# RP2040.net
KiCad netlist of a schematic drawn in Altium Designer
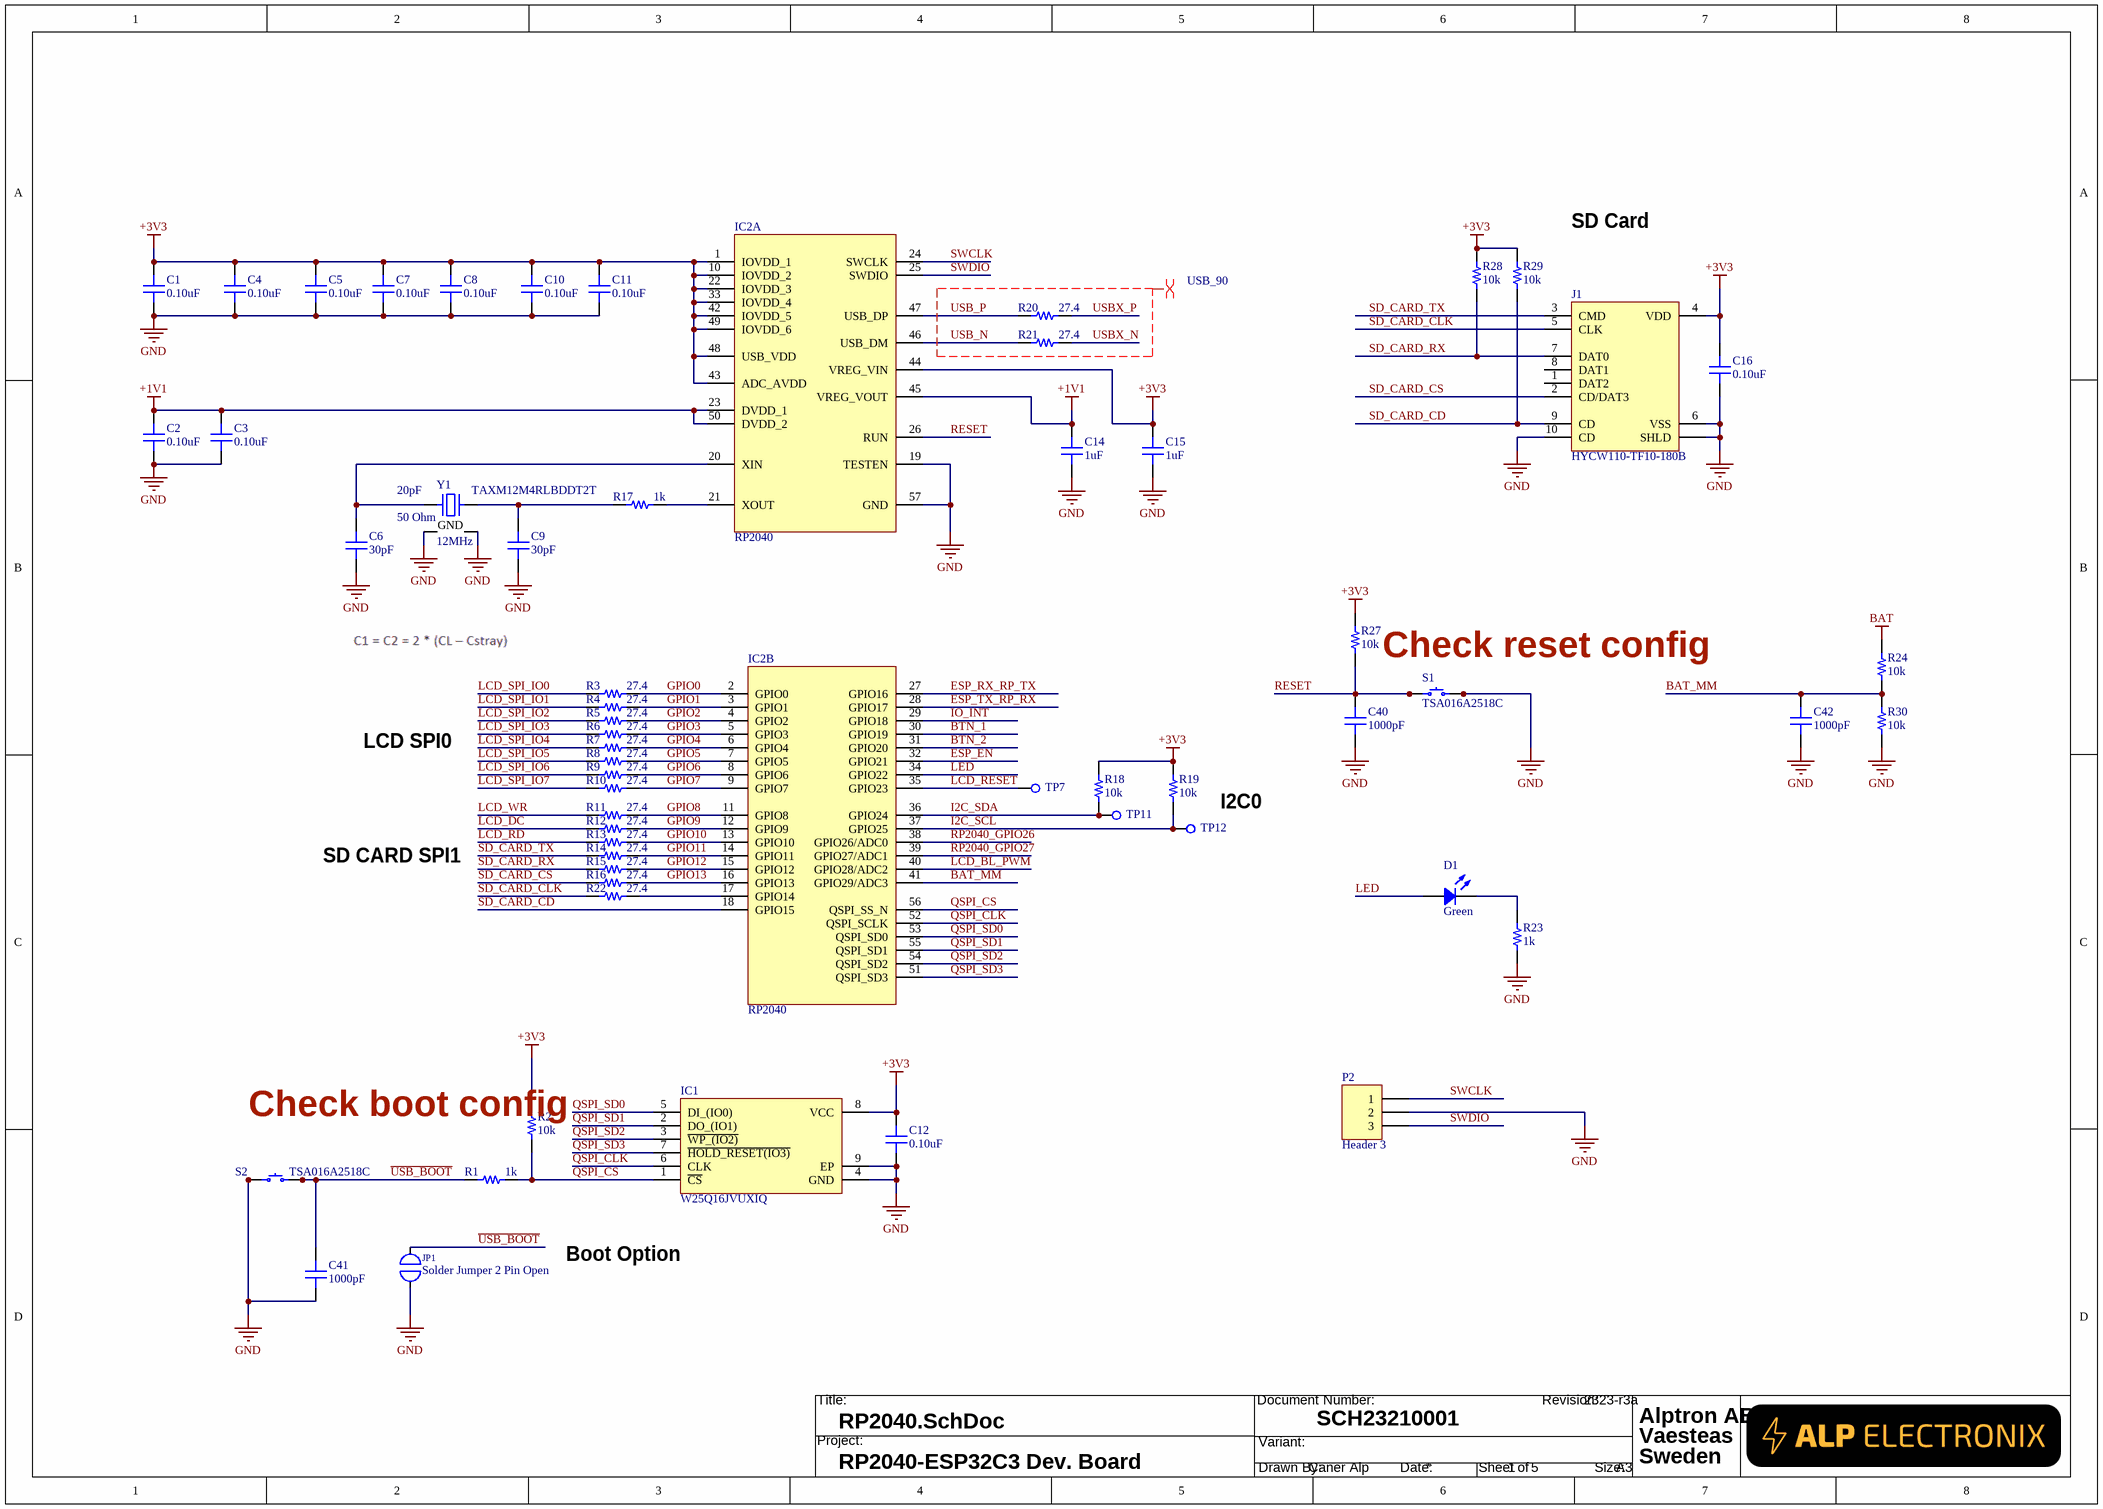
[diagram p0: RP2040.SchDoc]

(export (version "E")
  (design (tool "Eeschema 10.0.6"))
  (components
    (comp (ref "C1")
      (value "0.10uF")
      (footprint "CAP 0402/1005")
      (description "CAP CER 0.1UF 10V X5R 0402")
      (fields (field (name "PART NUMBER") "LMK105BJ104KV-F") (field (name "MANUFACTURER") "Taiyo Yuden"))
      (libsource (lib "Celestial Library Database") (part "Capacitor"))
    )
    (comp (ref "C2")
      (value "0.10uF")
      (footprint "CAP 0402/1005")
      (description "CAP CER 0.1UF 10V X5R 0402")
      (fields (field (name "PART NUMBER") "LMK105BJ104KV-F") (field (name "MANUFACTURER") "Taiyo Yuden"))
      (libsource (lib "Celestial Library Database") (part "Capacitor"))
    )
    (comp (ref "C3")
      (value "0.10uF")
      (footprint "CAP 0402/1005")
      (description "CAP CER 0.1UF 10V X5R 0402")
      (fields (field (name "PART NUMBER") "LMK105BJ104KV-F") (field (name "MANUFACTURER") "Taiyo Yuden"))
      (libsource (lib "Celestial Library Database") (part "Capacitor"))
    )
    (comp (ref "C4")
      (value "0.10uF")
      (footprint "CAP 0402/1005")
      (description "CAP CER 0.1UF 10V X5R 0402")
      (fields (field (name "PART NUMBER") "LMK105BJ104KV-F") (field (name "MANUFACTURER") "Taiyo Yuden"))
      (libsource (lib "Celestial Library Database") (part "Capacitor"))
    )
    (comp (ref "C5")
      (value "0.10uF")
      (footprint "CAP 0402/1005")
      (description "CAP CER 0.1UF 10V X5R 0402")
      (fields (field (name "PART NUMBER") "LMK105BJ104KV-F") (field (name "MANUFACTURER") "Taiyo Yuden"))
      (libsource (lib "Celestial Library Database") (part "Capacitor"))
    )
    (comp (ref "C6")
      (value "30pF")
      (footprint "CAP 0402/1005")
      (description "CAP CER 30PF 50V NP0 0402")
      (fields
        (field (name "PART NUMBER") "GRM1555C1H300JA01D")
        (field (name "MANUFACTURER") "Murata Electronics North America")
      )
      (libsource (lib "Celestial Library Database") (part "Capacitor"))
    )
    (comp (ref "C7")
      (value "0.10uF")
      (footprint "CAP 0402/1005")
      (description "CAP CER 0.1UF 10V X5R 0402")
      (fields (field (name "PART NUMBER") "LMK105BJ104KV-F") (field (name "MANUFACTURER") "Taiyo Yuden"))
      (libsource (lib "Celestial Library Database") (part "Capacitor"))
    )
    (comp (ref "C8")
      (value "0.10uF")
      (footprint "CAP 0402/1005")
      (description "CAP CER 0.1UF 10V X5R 0402")
      (fields (field (name "PART NUMBER") "LMK105BJ104KV-F") (field (name "MANUFACTURER") "Taiyo Yuden"))
      (libsource (lib "Celestial Library Database") (part "Capacitor"))
    )
    (comp (ref "C9")
      (value "30pF")
      (footprint "CAP 0402/1005")
      (description "CAP CER 30PF 50V NP0 0402")
      (fields
        (field (name "PART NUMBER") "GRM1555C1H300JA01D")
        (field (name "MANUFACTURER") "Murata Electronics North America")
      )
      (libsource (lib "Celestial Library Database") (part "Capacitor"))
    )
    (comp (ref "C10")
      (value "0.10uF")
      (footprint "CAP 0402/1005")
      (description "CAP CER 0.1UF 10V X5R 0402")
      (fields (field (name "PART NUMBER") "LMK105BJ104KV-F") (field (name "MANUFACTURER") "Taiyo Yuden"))
      (libsource (lib "Celestial Library Database") (part "Capacitor"))
    )
    (comp (ref "C11")
      (value "0.10uF")
      (footprint "CAP 0402/1005")
      (description "CAP CER 0.1UF 10V X5R 0402")
      (fields (field (name "PART NUMBER") "LMK105BJ104KV-F") (field (name "MANUFACTURER") "Taiyo Yuden"))
      (libsource (lib "Celestial Library Database") (part "Capacitor"))
    )
    (comp (ref "C12")
      (value "0.10uF")
      (footprint "CAP 0402/1005")
      (description "CAP CER 0.1UF 10V X5R 0402")
      (fields (field (name "PART NUMBER") "LMK105BJ104KV-F") (field (name "MANUFACTURER") "Taiyo Yuden"))
      (libsource (lib "Celestial Library Database") (part "Capacitor"))
    )
    (comp (ref "C14")
      (value "1uF")
      (footprint "CAP 0402/1005")
      (description "CAP CER 1UF 6.3V X7R 0402")
      (fields
        (field (name "PART NUMBER") "GRM155R70J105KA12D")
        (field (name "MANUFACTURER") "Murata Electronics North America")
      )
      (libsource (lib "Celestial Library Database") (part "Capacitor"))
    )
    (comp (ref "C15")
      (value "1uF")
      (footprint "CAP 0402/1005")
      (description "CAP CER 1UF 6.3V X7R 0402")
      (fields
        (field (name "PART NUMBER") "GRM155R70J105KA12D")
        (field (name "MANUFACTURER") "Murata Electronics North America")
      )
      (libsource (lib "Celestial Library Database") (part "Capacitor"))
    )
    (comp (ref "C16")
      (value "0.10uF")
      (footprint "CAP 0402/1005")
      (description "CAP CER 0.1UF 10V X5R 0402")
      (fields (field (name "PART NUMBER") "LMK105BJ104KV-F") (field (name "MANUFACTURER") "Taiyo Yuden"))
      (libsource (lib "Celestial Library Database") (part "Capacitor"))
    )
    (comp (ref "C40")
      (value "1000pF")
      (footprint "CAP 0402/1005")
      (description "CAP CER 1000PF 50V C0G 0402")
      (fields
        (field (name "PART NUMBER") "C1005C0G1H102J050BA")
        (field (name "MANUFACTURER") "TDK Corporation")
      )
      (libsource (lib "Celestial Library Database") (part "Capacitor"))
    )
    (comp (ref "C41")
      (value "1000pF")
      (footprint "CAP 0402/1005")
      (description "CAP CER 1000PF 50V C0G 0402")
      (fields
        (field (name "PART NUMBER") "C1005C0G1H102J050BA")
        (field (name "MANUFACTURER") "TDK Corporation")
      )
      (libsource (lib "Celestial Library Database") (part "Capacitor"))
    )
    (comp (ref "C42")
      (value "1000pF")
      (footprint "CAP 0402/1005")
      (description "CAP CER 1000PF 50V C0G 0402")
      (fields
        (field (name "PART NUMBER") "C1005C0G1H102J050BA")
        (field (name "MANUFACTURER") "TDK Corporation")
      )
      (libsource (lib "Celestial Library Database") (part "Capacitor"))
    )
    (comp (ref "D1")
      (value "Green")
      (footprint "LED 0603/1608 GREEN")
      (description "LED GREEN DIFFUSED 0603 SMD")
      (fields
        (field (name "PART NUMBER") "HSMQ-C191")
        (field (name "MANUFACTURER") "Avago Technologies US Inc.")
      )
      (libsource (lib "Celestial Library Database") (part "LED"))
    )
    (comp (ref "IC1")
      (value "W25Q16JVUXIQ")
      (footprint "RP2040_ESP32-C3 Dev Board PCB Lib:SON50P300X200X60-9N")
      (description "Integrated Circuit")
      (libsource (lib "RP2040_ESP32-C3 Dev Board SCH Lib") (part "W25Q16JVUXIQ"))
    )
    (comp (ref "IC2")
      (value "RP2040")
      (footprint "RP2040_ESP32-C3 Dev Board PCB Lib:QFN40P700X700X90-57N-D")
      (description "Integrated Circuit")
      (libsource (lib "RP2040_ESP32-C3 Dev Board SCH Lib") (part "RP2040"))
    )
    (comp (ref "J1")
      (value "HYCW110-TF10-180B")
      (footprint "HYCW110-TF10-180B")
      (description "MICRO SD PUSH/PUSH SMALL 8C")
      (fields (field (name "MANUFACTURER") "SHOU HAN"))
      (libsource (lib "RP2040_ESP32-C3 Dev Board SCH Lib") (part "HYCW110-TF10-180B"))
    )
    (comp (ref "JP1")
      (value "Solder Jumper 2 Pin Open")
      (footprint "Jumper:SolderJumper-2_P1.3mm_Open_RoundedPad1.0x1.5mm")
      (libsource (lib "Jumper") (part "SolderJumper_2_Open"))
    )
    (comp (ref "P2")
      (value "Header 3")
      (footprint "RP2040_ESP32-C3 Dev Board PCB Lib:3 Pads for SBW")
      (description "Header, 3-Pin")
      (fields (field (name "PUBLISHER") "Altium Limited"))
      (libsource (lib "Miscellaneous Connectors") (part "Header 3"))
    )
    (comp (ref "R1")
      (value "1k")
      (footprint "RES 0402/1005")
      (description "RES SMD 1K OHM 5% 1/10W 0402")
      (fields
        (field (name "PART NUMBER") "ERJ-2GEJ102X")
        (field (name "MANUFACTURER") "Panasonic Electronic Components")
      )
      (libsource (lib "Celestial Library Database") (part "Resistor"))
    )
    (comp (ref "R2")
      (value "10k")
      (footprint "RES 0402/1005")
      (description "RES SMD 10K OHM 5% 1/16W 0402")
      (fields (field (name "PART NUMBER") "RC0402JR-0710KL") (field (name "MANUFACTURER") "Yageo"))
      (libsource (lib "Celestial Library Database") (part "Resistor"))
    )
    (comp (ref "R3")
      (value "27.4")
      (footprint "RES 0402/1005")
      (description "RES SMD 27.4 OHM 1% 1/10W 0402")
      (fields
        (field (name "PART NUMBER") "ERJ-2RKF27R4X")
        (field (name "MANUFACTURER") "Panasonic Electronic Components")
      )
      (libsource (lib "Celestial Library Database") (part "Resistor"))
    )
    (comp (ref "R4")
      (value "27.4")
      (footprint "RES 0402/1005")
      (description "RES SMD 27.4 OHM 1% 1/10W 0402")
      (fields
        (field (name "PART NUMBER") "ERJ-2RKF27R4X")
        (field (name "MANUFACTURER") "Panasonic Electronic Components")
      )
      (libsource (lib "Celestial Library Database") (part "Resistor"))
    )
    (comp (ref "R5")
      (value "27.4")
      (footprint "RES 0402/1005")
      (description "RES SMD 27.4 OHM 1% 1/10W 0402")
      (fields
        (field (name "PART NUMBER") "ERJ-2RKF27R4X")
        (field (name "MANUFACTURER") "Panasonic Electronic Components")
      )
      (libsource (lib "Celestial Library Database") (part "Resistor"))
    )
    (comp (ref "R6")
      (value "27.4")
      (footprint "RES 0402/1005")
      (description "RES SMD 27.4 OHM 1% 1/10W 0402")
      (fields
        (field (name "PART NUMBER") "ERJ-2RKF27R4X")
        (field (name "MANUFACTURER") "Panasonic Electronic Components")
      )
      (libsource (lib "Celestial Library Database") (part "Resistor"))
    )
    (comp (ref "R7")
      (value "27.4")
      (footprint "RES 0402/1005")
      (description "RES SMD 27.4 OHM 1% 1/10W 0402")
      (fields
        (field (name "PART NUMBER") "ERJ-2RKF27R4X")
        (field (name "MANUFACTURER") "Panasonic Electronic Components")
      )
      (libsource (lib "Celestial Library Database") (part "Resistor"))
    )
    (comp (ref "R8")
      (value "27.4")
      (footprint "RES 0402/1005")
      (description "RES SMD 27.4 OHM 1% 1/10W 0402")
      (fields
        (field (name "PART NUMBER") "ERJ-2RKF27R4X")
        (field (name "MANUFACTURER") "Panasonic Electronic Components")
      )
      (libsource (lib "Celestial Library Database") (part "Resistor"))
    )
    (comp (ref "R9")
      (value "27.4")
      (footprint "RES 0402/1005")
      (description "RES SMD 27.4 OHM 1% 1/10W 0402")
      (fields
        (field (name "PART NUMBER") "ERJ-2RKF27R4X")
        (field (name "MANUFACTURER") "Panasonic Electronic Components")
      )
      (libsource (lib "Celestial Library Database") (part "Resistor"))
    )
    (comp (ref "R10")
      (value "27.4")
      (footprint "RES 0402/1005")
      (description "RES SMD 27.4 OHM 1% 1/10W 0402")
      (fields
        (field (name "PART NUMBER") "ERJ-2RKF27R4X")
        (field (name "MANUFACTURER") "Panasonic Electronic Components")
      )
      (libsource (lib "Celestial Library Database") (part "Resistor"))
    )
    (comp (ref "R11")
      (value "27.4")
      (footprint "RES 0402/1005")
      (description "RES SMD 27.4 OHM 1% 1/10W 0402")
      (fields
        (field (name "PART NUMBER") "ERJ-2RKF27R4X")
        (field (name "MANUFACTURER") "Panasonic Electronic Components")
      )
      (libsource (lib "Celestial Library Database") (part "Resistor"))
    )
    (comp (ref "R12")
      (value "27.4")
      (footprint "RES 0402/1005")
      (description "RES SMD 27.4 OHM 1% 1/10W 0402")
      (fields
        (field (name "PART NUMBER") "ERJ-2RKF27R4X")
        (field (name "MANUFACTURER") "Panasonic Electronic Components")
      )
      (libsource (lib "Celestial Library Database") (part "Resistor"))
    )
    (comp (ref "R13")
      (value "27.4")
      (footprint "RES 0402/1005")
      (description "RES SMD 27.4 OHM 1% 1/10W 0402")
      (fields
        (field (name "PART NUMBER") "ERJ-2RKF27R4X")
        (field (name "MANUFACTURER") "Panasonic Electronic Components")
      )
      (libsource (lib "Celestial Library Database") (part "Resistor"))
    )
    (comp (ref "R14")
      (value "27.4")
      (footprint "RES 0402/1005")
      (description "RES SMD 27.4 OHM 1% 1/10W 0402")
      (fields
        (field (name "PART NUMBER") "ERJ-2RKF27R4X")
        (field (name "MANUFACTURER") "Panasonic Electronic Components")
      )
      (libsource (lib "Celestial Library Database") (part "Resistor"))
    )
    (comp (ref "R15")
      (value "27.4")
      (footprint "RES 0402/1005")
      (description "RES SMD 27.4 OHM 1% 1/10W 0402")
      (fields
        (field (name "PART NUMBER") "ERJ-2RKF27R4X")
        (field (name "MANUFACTURER") "Panasonic Electronic Components")
      )
      (libsource (lib "Celestial Library Database") (part "Resistor"))
    )
    (comp (ref "R16")
      (value "27.4")
      (footprint "RES 0402/1005")
      (description "RES SMD 27.4 OHM 1% 1/10W 0402")
      (fields
        (field (name "PART NUMBER") "ERJ-2RKF27R4X")
        (field (name "MANUFACTURER") "Panasonic Electronic Components")
      )
      (libsource (lib "Celestial Library Database") (part "Resistor"))
    )
    (comp (ref "R17")
      (value "1k")
      (footprint "RES 0402/1005")
      (description "RES SMD 1K OHM 5% 1/10W 0402")
      (fields
        (field (name "PART NUMBER") "ERJ-2GEJ102X")
        (field (name "MANUFACTURER") "Panasonic Electronic Components")
      )
      (libsource (lib "Celestial Library Database") (part "Resistor"))
    )
    (comp (ref "R18")
      (value "10k")
      (footprint "RES 0402/1005")
      (description "RES SMD 10K OHM 5% 1/16W 0402")
      (fields (field (name "PART NUMBER") "RC0402JR-0710KL") (field (name "MANUFACTURER") "Yageo"))
      (libsource (lib "Celestial Library Database") (part "Resistor"))
    )
    (comp (ref "R19")
      (value "10k")
      (footprint "RES 0402/1005")
      (description "RES SMD 10K OHM 5% 1/16W 0402")
      (fields (field (name "PART NUMBER") "RC0402JR-0710KL") (field (name "MANUFACTURER") "Yageo"))
      (libsource (lib "Celestial Library Database") (part "Resistor"))
    )
    (comp (ref "R20")
      (value "27.4")
      (footprint "RES 0402/1005")
      (description "RES SMD 27.4 OHM 1% 1/10W 0402")
      (fields
        (field (name "PART NUMBER") "ERJ-2RKF27R4X")
        (field (name "MANUFACTURER") "Panasonic Electronic Components")
      )
      (libsource (lib "Celestial Library Database") (part "Resistor"))
    )
    (comp (ref "R21")
      (value "27.4")
      (footprint "RES 0402/1005")
      (description "RES SMD 27.4 OHM 1% 1/10W 0402")
      (fields
        (field (name "PART NUMBER") "ERJ-2RKF27R4X")
        (field (name "MANUFACTURER") "Panasonic Electronic Components")
      )
      (libsource (lib "Celestial Library Database") (part "Resistor"))
    )
    (comp (ref "R22")
      (value "27.4")
      (footprint "RES 0402/1005")
      (description "RES SMD 27.4 OHM 1% 1/10W 0402")
      (fields
        (field (name "PART NUMBER") "ERJ-2RKF27R4X")
        (field (name "MANUFACTURER") "Panasonic Electronic Components")
      )
      (libsource (lib "Celestial Library Database") (part "Resistor"))
    )
    (comp (ref "R23")
      (value "1k")
      (footprint "RES 0402/1005")
      (description "RES SMD 1K OHM 5% 1/10W 0402")
      (fields
        (field (name "PART NUMBER") "ERJ-2GEJ102X")
        (field (name "MANUFACTURER") "Panasonic Electronic Components")
      )
      (libsource (lib "Celestial Library Database") (part "Resistor"))
    )
    (comp (ref "R24")
      (value "10k")
      (footprint "RES 0402/1005")
      (description "RES SMD 10K OHM 5% 1/16W 0402")
      (fields (field (name "PART NUMBER") "RC0402JR-0710KL") (field (name "MANUFACTURER") "Yageo"))
      (libsource (lib "Celestial Library Database") (part "Resistor"))
    )
    (comp (ref "R27")
      (value "10k")
      (footprint "RES 0402/1005")
      (description "RES SMD 10K OHM 5% 1/16W 0402")
      (fields (field (name "PART NUMBER") "RC0402JR-0710KL") (field (name "MANUFACTURER") "Yageo"))
      (libsource (lib "Celestial Library Database") (part "Resistor"))
    )
    (comp (ref "R28")
      (value "10k")
      (footprint "RES 0402/1005")
      (description "RES SMD 10K OHM 5% 1/16W 0402")
      (fields (field (name "PART NUMBER") "RC0402JR-0710KL") (field (name "MANUFACTURER") "Yageo"))
      (libsource (lib "Celestial Library Database") (part "Resistor"))
    )
    (comp (ref "R29")
      (value "10k")
      (footprint "RES 0402/1005")
      (description "RES SMD 10K OHM 5% 1/16W 0402")
      (fields (field (name "PART NUMBER") "RC0402JR-0710KL") (field (name "MANUFACTURER") "Yageo"))
      (libsource (lib "Celestial Library Database") (part "Resistor"))
    )
    (comp (ref "R30")
      (value "10k")
      (footprint "RES 0402/1005")
      (description "RES SMD 10K OHM 5% 1/16W 0402")
      (fields (field (name "PART NUMBER") "RC0402JR-0710KL") (field (name "MANUFACTURER") "Yageo"))
      (libsource (lib "Celestial Library Database") (part "Resistor"))
    )
    (comp (ref "S1")
      (value "TSA016A2518C")
      (footprint "RP2040_ESP32-C3 Dev Board PCB Lib:TSA016A2518C")
      (description "SWITCH TACTILE SPST-NO 0.05A 16V")
      (fields (field (name "MANUFACTURER") "C&K"))
      (libsource (lib "Celestial Altium Library - altium_library") (part "SPST-NO 4 PIN"))
    )
    (comp (ref "S2")
      (value "TSA016A2518C")
      (footprint "RP2040_ESP32-C3 Dev Board PCB Lib:TSA016A2518C")
      (description "SWITCH TACTILE SPST-NO 0.05A 16V")
      (fields (field (name "MANUFACTURER") "C&K"))
      (libsource (lib "Celestial Altium Library - altium_library") (part "SPST-NO 4 PIN"))
    )
    (comp (ref "TP7")
      (value "RCT-0C")
      (footprint "RP2040_ESP32-C3 Dev Board PCB Lib:TestPoint 1mm")
      (description "0805 PROBE PAD")
      (fields (field (name "MANUFACTURER") "TE Connectivity AMP Connectors"))
      (libsource (lib "Celestial Library Database") (part "Test Point"))
    )
    (comp (ref "TP11")
      (value "RCT-0C")
      (footprint "RP2040_ESP32-C3 Dev Board PCB Lib:TestPoint 1mm")
      (description "0805 PROBE PAD")
      (fields (field (name "MANUFACTURER") "TE Connectivity AMP Connectors"))
      (libsource (lib "Celestial Library Database") (part "Test Point"))
    )
    (comp (ref "TP12")
      (value "RCT-0C")
      (footprint "RP2040_ESP32-C3 Dev Board PCB Lib:TestPoint 1mm")
      (description "0805 PROBE PAD")
      (fields (field (name "MANUFACTURER") "TE Connectivity AMP Connectors"))
      (libsource (lib "Celestial Library Database") (part "Test Point"))
    )
    (comp (ref "Y1")
      (value "12MHz")
      (footprint "NDK NX3225SA")
      (description "CRYSTAL 12.0000MHZ 8PF SMD")
      (fields
        (field (name "PART NUMBER") "TAXM12M4RLBDDT2T")
        (field (name "MANUFACTURER") "NDK")
        (field (name "LOAD CAPACITANCE") "20pF")
        (field (name "ESR") "50 Ohm")
      )
      (libsource (lib "Celestial Library Database") (part "NDK Crystal NX3225SA"))
    )
  )
  (nets
    (net (code "1") (name "+1V1") (class "Default")
      (node (ref "C14") (pin "2") (pinfunction "2_2") (pintype "passive"))
      (node (ref "C2") (pin "2") (pinfunction "2_2") (pintype "passive"))
      (node (ref "C3") (pin "2") (pinfunction "2_2") (pintype "passive"))
      (node (ref "IC2") (pin "23") (pinfunction "DVDD_1_23") (pintype "passive"))
      (node (ref "IC2") (pin "45") (pinfunction "VREG_VOUT_45") (pintype "passive"))
      (node (ref "IC2") (pin "50") (pinfunction "DVDD_2_50") (pintype "passive"))
    )
    (net (code "2") (name "+3V3") (class "Default")
      (node (ref "C1") (pin "2") (pinfunction "2_2") (pintype "passive"))
      (node (ref "C10") (pin "2") (pinfunction "2_2") (pintype "passive"))
      (node (ref "C11") (pin "2") (pinfunction "2_2") (pintype "passive"))
      (node (ref "C12") (pin "2") (pinfunction "2_2") (pintype "passive"))
      (node (ref "C15") (pin "2") (pinfunction "2_2") (pintype "passive"))
      (node (ref "C16") (pin "2") (pinfunction "2_2") (pintype "passive"))
      (node (ref "C4") (pin "2") (pinfunction "2_2") (pintype "passive"))
      (node (ref "C5") (pin "2") (pinfunction "2_2") (pintype "passive"))
      (node (ref "C7") (pin "2") (pinfunction "2_2") (pintype "passive"))
      (node (ref "C8") (pin "2") (pinfunction "2_2") (pintype "passive"))
      (node (ref "IC1") (pin "8") (pinfunction "VCC_8") (pintype "passive"))
      (node (ref "IC2") (pin "1") (pinfunction "IOVDD_1_1") (pintype "passive"))
      (node (ref "IC2") (pin "10") (pinfunction "IOVDD_2_10") (pintype "passive"))
      (node (ref "IC2") (pin "22") (pinfunction "IOVDD_3_22") (pintype "passive"))
      (node (ref "IC2") (pin "33") (pinfunction "IOVDD_4_33") (pintype "passive"))
      (node (ref "IC2") (pin "42") (pinfunction "IOVDD_5_42") (pintype "passive"))
      (node (ref "IC2") (pin "43") (pinfunction "ADC_AVDD_43") (pintype "passive"))
      (node (ref "IC2") (pin "44") (pinfunction "VREG_VIN_44") (pintype "passive"))
      (node (ref "IC2") (pin "48") (pinfunction "USB_VDD_48") (pintype "passive"))
      (node (ref "IC2") (pin "49") (pinfunction "IOVDD_6_49") (pintype "passive"))
      (node (ref "J1") (pin "4") (pinfunction "VDD_4") (pintype "passive"))
      (node (ref "R18") (pin "2") (pinfunction "2_2") (pintype "passive"))
      (node (ref "R19") (pin "2") (pinfunction "2_2") (pintype "passive"))
      (node (ref "R2") (pin "2") (pinfunction "2_2") (pintype "passive"))
      (node (ref "R27") (pin "2") (pinfunction "2_2") (pintype "passive"))
      (node (ref "R28") (pin "2") (pinfunction "2_2") (pintype "passive"))
      (node (ref "R29") (pin "2") (pinfunction "2_2") (pintype "passive"))
    )
    (net (code "3") (name "/BAT_MM") (class "Default")
      (node (ref "C42") (pin "2") (pinfunction "2_2") (pintype "passive"))
      (node (ref "IC2") (pin "41") (pinfunction "GPIO29/ADC3_41") (pintype "passive"))
      (node (ref "R24") (pin "1") (pinfunction "1_1") (pintype "passive"))
      (node (ref "R30") (pin "2") (pinfunction "2_2") (pintype "passive"))
    )
    (net (code "4") (name "/BTN_1") (class "Default")
      (node (ref "IC2") (pin "30") (pinfunction "GPIO19_30") (pintype "passive"))
    )
    (net (code "5") (name "/BTN_2") (class "Default")
      (node (ref "IC2") (pin "31") (pinfunction "GPIO20_31") (pintype "passive"))
    )
    (net (code "6") (name "/ESP_EN") (class "Default")
      (node (ref "IC2") (pin "32") (pinfunction "GPIO21_32") (pintype "passive"))
    )
    (net (code "7") (name "/ESP_RX_RP_TX") (class "Default")
      (node (ref "IC2") (pin "27") (pinfunction "GPIO16_27") (pintype "passive"))
    )
    (net (code "8") (name "/ESP_TX_RP_RX") (class "Default")
      (node (ref "IC2") (pin "28") (pinfunction "GPIO17_28") (pintype "passive"))
    )
    (net (code "9") (name "/GPIO0") (class "Default")
      (node (ref "IC2") (pin "2") (pinfunction "GPIO0_2") (pintype "passive"))
      (node (ref "R3") (pin "2") (pinfunction "2_2") (pintype "passive"))
    )
    (net (code "10") (name "/GPIO1") (class "Default")
      (node (ref "IC2") (pin "3") (pinfunction "GPIO1_3") (pintype "passive"))
      (node (ref "R4") (pin "2") (pinfunction "2_2") (pintype "passive"))
    )
    (net (code "11") (name "/GPIO2") (class "Default")
      (node (ref "IC2") (pin "4") (pinfunction "GPIO2_4") (pintype "passive"))
      (node (ref "R5") (pin "2") (pinfunction "2_2") (pintype "passive"))
    )
    (net (code "12") (name "/GPIO3") (class "Default")
      (node (ref "IC2") (pin "5") (pinfunction "GPIO3_5") (pintype "passive"))
      (node (ref "R6") (pin "2") (pinfunction "2_2") (pintype "passive"))
    )
    (net (code "13") (name "/GPIO4") (class "Default")
      (node (ref "IC2") (pin "6") (pinfunction "GPIO4_6") (pintype "passive"))
      (node (ref "R7") (pin "2") (pinfunction "2_2") (pintype "passive"))
    )
    (net (code "14") (name "/GPIO5") (class "Default")
      (node (ref "IC2") (pin "7") (pinfunction "GPIO5_7") (pintype "passive"))
      (node (ref "R8") (pin "2") (pinfunction "2_2") (pintype "passive"))
    )
    (net (code "15") (name "/GPIO6") (class "Default")
      (node (ref "IC2") (pin "8") (pinfunction "GPIO6_8") (pintype "passive"))
      (node (ref "R9") (pin "2") (pinfunction "2_2") (pintype "passive"))
    )
    (net (code "16") (name "/GPIO7") (class "Default")
      (node (ref "IC2") (pin "9") (pinfunction "GPIO7_9") (pintype "passive"))
      (node (ref "R10") (pin "2") (pinfunction "2_2") (pintype "passive"))
    )
    (net (code "17") (name "/GPIO8") (class "Default")
      (node (ref "IC2") (pin "11") (pinfunction "GPIO8_11") (pintype "passive"))
      (node (ref "R11") (pin "2") (pinfunction "2_2") (pintype "passive"))
    )
    (net (code "18") (name "/GPIO9") (class "Default")
      (node (ref "IC2") (pin "12") (pinfunction "GPIO9_12") (pintype "passive"))
      (node (ref "R12") (pin "2") (pinfunction "2_2") (pintype "passive"))
    )
    (net (code "19") (name "/GPIO10") (class "Default")
      (node (ref "IC2") (pin "13") (pinfunction "GPIO10_13") (pintype "passive"))
      (node (ref "R13") (pin "2") (pinfunction "2_2") (pintype "passive"))
    )
    (net (code "20") (name "/GPIO11") (class "Default")
      (node (ref "IC2") (pin "14") (pinfunction "GPIO11_14") (pintype "passive"))
      (node (ref "R14") (pin "2") (pinfunction "2_2") (pintype "passive"))
    )
    (net (code "21") (name "/GPIO12") (class "Default")
      (node (ref "IC2") (pin "15") (pinfunction "GPIO12_15") (pintype "passive"))
      (node (ref "R15") (pin "2") (pinfunction "2_2") (pintype "passive"))
    )
    (net (code "22") (name "/GPIO13") (class "Default")
      (node (ref "IC2") (pin "16") (pinfunction "GPIO13_16") (pintype "passive"))
      (node (ref "R16") (pin "2") (pinfunction "2_2") (pintype "passive"))
    )
    (net (code "23") (name "/I2C_SCL") (class "Default")
      (node (ref "IC2") (pin "37") (pinfunction "GPIO25_37") (pintype "passive"))
      (node (ref "R19") (pin "1") (pinfunction "1_1") (pintype "passive"))
      (node (ref "TP12") (pin "1") (pinfunction "TP_1") (pintype "passive"))
    )
    (net (code "24") (name "/I2C_SDA") (class "Default")
      (node (ref "IC2") (pin "36") (pinfunction "GPIO24_36") (pintype "passive"))
      (node (ref "R18") (pin "1") (pinfunction "1_1") (pintype "passive"))
      (node (ref "TP11") (pin "1") (pinfunction "TP_1") (pintype "passive"))
    )
    (net (code "25") (name "/IO_INT") (class "Default")
      (node (ref "IC2") (pin "29") (pinfunction "GPIO18_29") (pintype "passive"))
    )
    (net (code "26") (name "/LCD_BL_PWM") (class "Default")
      (node (ref "IC2") (pin "40") (pinfunction "GPIO28/ADC2_40") (pintype "passive"))
    )
    (net (code "27") (name "/LCD_DC") (class "Default")
      (node (ref "R12") (pin "1") (pinfunction "1_1") (pintype "passive"))
    )
    (net (code "28") (name "/LCD_RD") (class "Default")
      (node (ref "R13") (pin "1") (pinfunction "1_1") (pintype "passive"))
    )
    (net (code "29") (name "/LCD_RESET") (class "Default")
      (node (ref "IC2") (pin "35") (pinfunction "GPIO23_35") (pintype "passive"))
      (node (ref "TP7") (pin "1") (pinfunction "TP_1") (pintype "passive"))
    )
    (net (code "30") (name "/LCD_SPI_IO0") (class "Default")
      (node (ref "R3") (pin "1") (pinfunction "1_1") (pintype "passive"))
    )
    (net (code "31") (name "/LCD_SPI_IO1") (class "Default")
      (node (ref "R4") (pin "1") (pinfunction "1_1") (pintype "passive"))
    )
    (net (code "32") (name "/LCD_SPI_IO2") (class "Default")
      (node (ref "R5") (pin "1") (pinfunction "1_1") (pintype "passive"))
    )
    (net (code "33") (name "/LCD_SPI_IO3") (class "Default")
      (node (ref "R6") (pin "1") (pinfunction "1_1") (pintype "passive"))
    )
    (net (code "34") (name "/LCD_SPI_IO4") (class "Default")
      (node (ref "R7") (pin "1") (pinfunction "1_1") (pintype "passive"))
    )
    (net (code "35") (name "/LCD_SPI_IO5") (class "Default")
      (node (ref "R8") (pin "1") (pinfunction "1_1") (pintype "passive"))
    )
    (net (code "36") (name "/LCD_SPI_IO6") (class "Default")
      (node (ref "R9") (pin "1") (pinfunction "1_1") (pintype "passive"))
    )
    (net (code "37") (name "/LCD_SPI_IO7") (class "Default")
      (node (ref "R10") (pin "1") (pinfunction "1_1") (pintype "passive"))
    )
    (net (code "38") (name "/LCD_WR") (class "Default")
      (node (ref "R11") (pin "1") (pinfunction "1_1") (pintype "passive"))
    )
    (net (code "39") (name "/LED") (class "Default")
      (node (ref "D1") (pin "1") (pinfunction "1_1") (pintype "passive"))
      (node (ref "IC2") (pin "34") (pinfunction "GPIO22_34") (pintype "passive"))
    )
    (net (code "40") (name "/QSPI_CLK") (class "Default")
      (node (ref "IC1") (pin "6") (pinfunction "CLK_6") (pintype "passive"))
      (node (ref "IC2") (pin "52") (pinfunction "QSPI_SCLK_52") (pintype "passive"))
    )
    (net (code "41") (name "/QSPI_CS") (class "Default")
      (node (ref "IC1") (pin "1") (pinfunction "~{CS}_1") (pintype "passive"))
      (node (ref "IC2") (pin "56") (pinfunction "QSPI_SS_N_56") (pintype "passive"))
      (node (ref "R1") (pin "2") (pinfunction "2_2") (pintype "passive"))
      (node (ref "R2") (pin "1") (pinfunction "1_1") (pintype "passive"))
    )
    (net (code "42") (name "/QSPI_SD0") (class "Default")
      (node (ref "IC1") (pin "5") (pinfunction "DI_(IO0)_5") (pintype "passive"))
      (node (ref "IC2") (pin "53") (pinfunction "QSPI_SD0_53") (pintype "passive"))
    )
    (net (code "43") (name "/QSPI_SD1") (class "Default")
      (node (ref "IC1") (pin "2") (pinfunction "DO_(IO1)_2") (pintype "passive"))
      (node (ref "IC2") (pin "55") (pinfunction "QSPI_SD1_55") (pintype "passive"))
    )
    (net (code "44") (name "/QSPI_SD2") (class "Default")
      (node (ref "IC1") (pin "3") (pinfunction "~{WP_(IO2)}_3") (pintype "passive"))
      (node (ref "IC2") (pin "54") (pinfunction "QSPI_SD2_54") (pintype "passive"))
    )
    (net (code "45") (name "/QSPI_SD3") (class "Default")
      (node (ref "IC1") (pin "7") (pinfunction "~{HOLD_RESET(IO3)}_7") (pintype "passive"))
      (node (ref "IC2") (pin "51") (pinfunction "QSPI_SD3_51") (pintype "passive"))
    )
    (net (code "46") (name "/RESET") (class "Default")
      (node (ref "C40") (pin "2") (pinfunction "2_2") (pintype "passive"))
      (node (ref "IC2") (pin "26") (pinfunction "RUN_26") (pintype "passive"))
      (node (ref "R27") (pin "1") (pinfunction "1_1") (pintype "passive"))
      (node (ref "S1") (pin "1") (pinfunction "1_1") (pintype "passive"))
      (node (ref "S1") (pin "2") (pinfunction "2_2") (pintype "passive"))
    )
    (net (code "47") (name "/RP2040_GPIO26") (class "Default")
      (node (ref "IC2") (pin "38") (pinfunction "GPIO26/ADC0_38") (pintype "passive"))
    )
    (net (code "48") (name "/RP2040_GPIO27") (class "Default")
      (node (ref "IC2") (pin "39") (pinfunction "GPIO27/ADC1_39") (pintype "passive"))
    )
    (net (code "49") (name "/SD_CARD_CD") (class "Default")
      (node (ref "IC2") (pin "18") (pinfunction "GPIO15_18") (pintype "passive"))
      (node (ref "J1") (pin "9") (pinfunction "CD_9") (pintype "passive"))
      (node (ref "R29") (pin "1") (pinfunction "1_1") (pintype "passive"))
    )
    (net (code "50") (name "/SD_CARD_CLK") (class "Default")
      (node (ref "J1") (pin "5") (pinfunction "CLK_5") (pintype "passive"))
      (node (ref "R22") (pin "1") (pinfunction "1_1") (pintype "passive"))
    )
    (net (code "51") (name "/SD_CARD_CS") (class "Default")
      (node (ref "J1") (pin "2") (pinfunction "CD/DAT3_2") (pintype "passive"))
      (node (ref "R16") (pin "1") (pinfunction "1_1") (pintype "passive"))
    )
    (net (code "52") (name "/SD_CARD_RX") (class "Default")
      (node (ref "J1") (pin "7") (pinfunction "DAT0_7") (pintype "passive"))
      (node (ref "R15") (pin "1") (pinfunction "1_1") (pintype "passive"))
      (node (ref "R28") (pin "1") (pinfunction "1_1") (pintype "passive"))
    )
    (net (code "53") (name "/SD_CARD_TX") (class "Default")
      (node (ref "J1") (pin "3") (pinfunction "CMD_3") (pintype "passive"))
      (node (ref "R14") (pin "1") (pinfunction "1_1") (pintype "passive"))
    )
    (net (code "54") (name "/SWCLK") (class "Default")
      (node (ref "IC2") (pin "24") (pinfunction "SWCLK_24") (pintype "passive"))
      (node (ref "P2") (pin "1") (pinfunction "1_1") (pintype "passive"))
    )
    (net (code "55") (name "/SWDIO") (class "Default")
      (node (ref "IC2") (pin "25") (pinfunction "SWDIO_25") (pintype "passive"))
      (node (ref "P2") (pin "3") (pinfunction "3_3") (pintype "passive"))
    )
    (net (code "56") (name "/USBX_N") (class "Default")
      (node (ref "R21") (pin "2") (pinfunction "2_2") (pintype "passive"))
    )
    (net (code "57") (name "/USBX_P") (class "Default")
      (node (ref "R20") (pin "2") (pinfunction "2_2") (pintype "passive"))
    )
    (net (code "58") (name "/USB_BOOT") (class "Default")
      (node (ref "C41") (pin "2") (pinfunction "2_2") (pintype "passive"))
      (node (ref "JP1") (pin "2") (pinfunction "B_2") (pintype "passive"))
      (node (ref "R1") (pin "1") (pinfunction "1_1") (pintype "passive"))
      (node (ref "S2") (pin "3") (pinfunction "3_3") (pintype "passive"))
      (node (ref "S2") (pin "4") (pinfunction "4_4") (pintype "passive"))
    )
    (net (code "59") (name "/USB_N") (class "Default")
      (node (ref "IC2") (pin "46") (pinfunction "USB_DM_46") (pintype "passive"))
      (node (ref "R21") (pin "1") (pinfunction "1_1") (pintype "passive"))
    )
    (net (code "60") (name "/USB_P") (class "Default")
      (node (ref "IC2") (pin "47") (pinfunction "USB_DP_47") (pintype "passive"))
      (node (ref "R20") (pin "1") (pinfunction "1_1") (pintype "passive"))
    )
    (net (code "61") (name "BAT") (class "Default")
      (node (ref "R24") (pin "2") (pinfunction "2_2") (pintype "passive"))
    )
    (net (code "62") (name "GND") (class "Default")
      (node (ref "C1") (pin "1") (pinfunction "1_1") (pintype "passive"))
      (node (ref "C10") (pin "1") (pinfunction "1_1") (pintype "passive"))
      (node (ref "C11") (pin "1") (pinfunction "1_1") (pintype "passive"))
      (node (ref "C12") (pin "1") (pinfunction "1_1") (pintype "passive"))
      (node (ref "C14") (pin "1") (pinfunction "1_1") (pintype "passive"))
      (node (ref "C15") (pin "1") (pinfunction "1_1") (pintype "passive"))
      (node (ref "C16") (pin "1") (pinfunction "1_1") (pintype "passive"))
      (node (ref "C2") (pin "1") (pinfunction "1_1") (pintype "passive"))
      (node (ref "C3") (pin "1") (pinfunction "1_1") (pintype "passive"))
      (node (ref "C4") (pin "1") (pinfunction "1_1") (pintype "passive"))
      (node (ref "C40") (pin "1") (pinfunction "1_1") (pintype "passive"))
      (node (ref "C41") (pin "1") (pinfunction "1_1") (pintype "passive"))
      (node (ref "C42") (pin "1") (pinfunction "1_1") (pintype "passive"))
      (node (ref "C5") (pin "1") (pinfunction "1_1") (pintype "passive"))
      (node (ref "C6") (pin "1") (pinfunction "1_1") (pintype "passive"))
      (node (ref "C7") (pin "1") (pinfunction "1_1") (pintype "passive"))
      (node (ref "C8") (pin "1") (pinfunction "1_1") (pintype "passive"))
      (node (ref "C9") (pin "1") (pinfunction "1_1") (pintype "passive"))
      (node (ref "IC1") (pin "4") (pinfunction "GND_4") (pintype "passive"))
      (node (ref "IC1") (pin "9") (pinfunction "EP_9") (pintype "passive"))
      (node (ref "IC2") (pin "19") (pinfunction "TESTEN_19") (pintype "passive"))
      (node (ref "IC2") (pin "57") (pinfunction "GND_57") (pintype "passive"))
      (node (ref "J1") (pin "10") (pinfunction "CD_10") (pintype "passive"))
      (node (ref "J1") (pin "6") (pinfunction "VSS_6") (pintype "passive"))
      (node (ref "J1") (pin "S") (pinfunction "SHLD_S") (pintype "passive"))
      (node (ref "JP1") (pin "1") (pinfunction "A_1") (pintype "passive"))
      (node (ref "P2") (pin "2") (pinfunction "2_2") (pintype "passive"))
      (node (ref "R23") (pin "1") (pinfunction "1_1") (pintype "passive"))
      (node (ref "R30") (pin "1") (pinfunction "1_1") (pintype "passive"))
      (node (ref "S1") (pin "3") (pinfunction "3_3") (pintype "passive"))
      (node (ref "S1") (pin "4") (pinfunction "4_4") (pintype "passive"))
      (node (ref "S2") (pin "1") (pinfunction "1_1") (pintype "passive"))
      (node (ref "S2") (pin "2") (pinfunction "2_2") (pintype "passive"))
      (node (ref "Y1") (pin "2") (pinfunction "GND_2") (pintype "passive"))
      (node (ref "Y1") (pin "4") (pinfunction "GND_4") (pintype "passive"))
    )
    (net (code "63") (name "Net-(C9-Pad2)") (class "Default")
      (node (ref "C9") (pin "2") (pinfunction "2_2") (pintype "passive"))
      (node (ref "R17") (pin "1") (pinfunction "1_1") (pintype "passive"))
      (node (ref "Y1") (pin "3") (pinfunction "3_3") (pintype "passive"))
    )
    (net (code "64") (name "Net-(D1-Pad2)") (class "Default")
      (node (ref "D1") (pin "2") (pinfunction "2_2") (pintype "passive"))
      (node (ref "R23") (pin "2") (pinfunction "2_2") (pintype "passive"))
    )
    (net (code "65") (name "Net-(IC2A-XIN)") (class "Default")
      (node (ref "C6") (pin "2") (pinfunction "2_2") (pintype "passive"))
      (node (ref "IC2") (pin "20") (pinfunction "XIN_20") (pintype "passive"))
      (node (ref "Y1") (pin "1") (pinfunction "1_1") (pintype "passive"))
    )
    (net (code "66") (name "Net-(IC2A-XOUT)") (class "Default")
      (node (ref "IC2") (pin "21") (pinfunction "XOUT_21") (pintype "passive"))
      (node (ref "R17") (pin "2") (pinfunction "2_2") (pintype "passive"))
    )
    (net (code "67") (name "Net-(IC2B-GPIO14)") (class "Default")
      (node (ref "IC2") (pin "17") (pinfunction "GPIO14_17") (pintype "passive"))
      (node (ref "R22") (pin "2") (pinfunction "2_2") (pintype "passive"))
    )
    (net (code "68") (name "unconnected-(J1-DAT1-Pad8)") (class "Default")
      (node (ref "J1") (pin "8") (pinfunction "DAT1_8") (pintype "passive"))
    )
    (net (code "69") (name "unconnected-(J1-DAT2-Pad1)") (class "Default")
      (node (ref "J1") (pin "1") (pinfunction "DAT2_1") (pintype "passive"))
    )
  )
)
